# NearField_E_Probe.net
KiCad netlist of a schematic drawn in Altium Designer
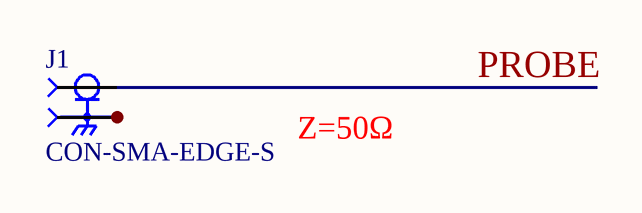
[diagram p0: NearField_E_Probe.SchDoc]

(export (version "E")
  (design (tool "Eeschema 10.0.6"))
  (components
    (comp (ref "J1")
      (value "CON-SMA-EDGE-S")
      (footprint "RFSOLUTIONS_CON-SMA-EDGE-S")
      (description "SMA Connector Jack, Female Socket - Board Edge, End Launch Solder")
      (fields (field (name "MF") "RF Solutions") (field (name "DIGI-KEY_PART_NUMBER") "CON-SMA-EDGE-S-ND"))
      (libsource (lib "CON-SMA-EDGE-S") (part "CON-SMA-EDGE-S"))
    )
  )
  (nets
    (net (code "1") (name "Net-(J1-2-PadG1)") (class "Default")
      (node (ref "J1") (pin "G1") (pinfunction "2_G1") (pintype "passive"))
      (node (ref "J1") (pin "G2") (pinfunction "2_G2") (pintype "passive"))
      (node (ref "J1") (pin "G3") (pinfunction "2_G3") (pintype "passive"))
      (node (ref "J1") (pin "G4") (pinfunction "2_G4") (pintype "passive"))
    )
    (net (code "2") (name "unconnected-(J1-Pad1)") (class "Default")
      (node (ref "J1") (pin "1") (pinfunction "1_1") (pintype "passive"))
    )
  )
)
